# Connectors.net
KiCad netlist of a schematic drawn in Altium Designer
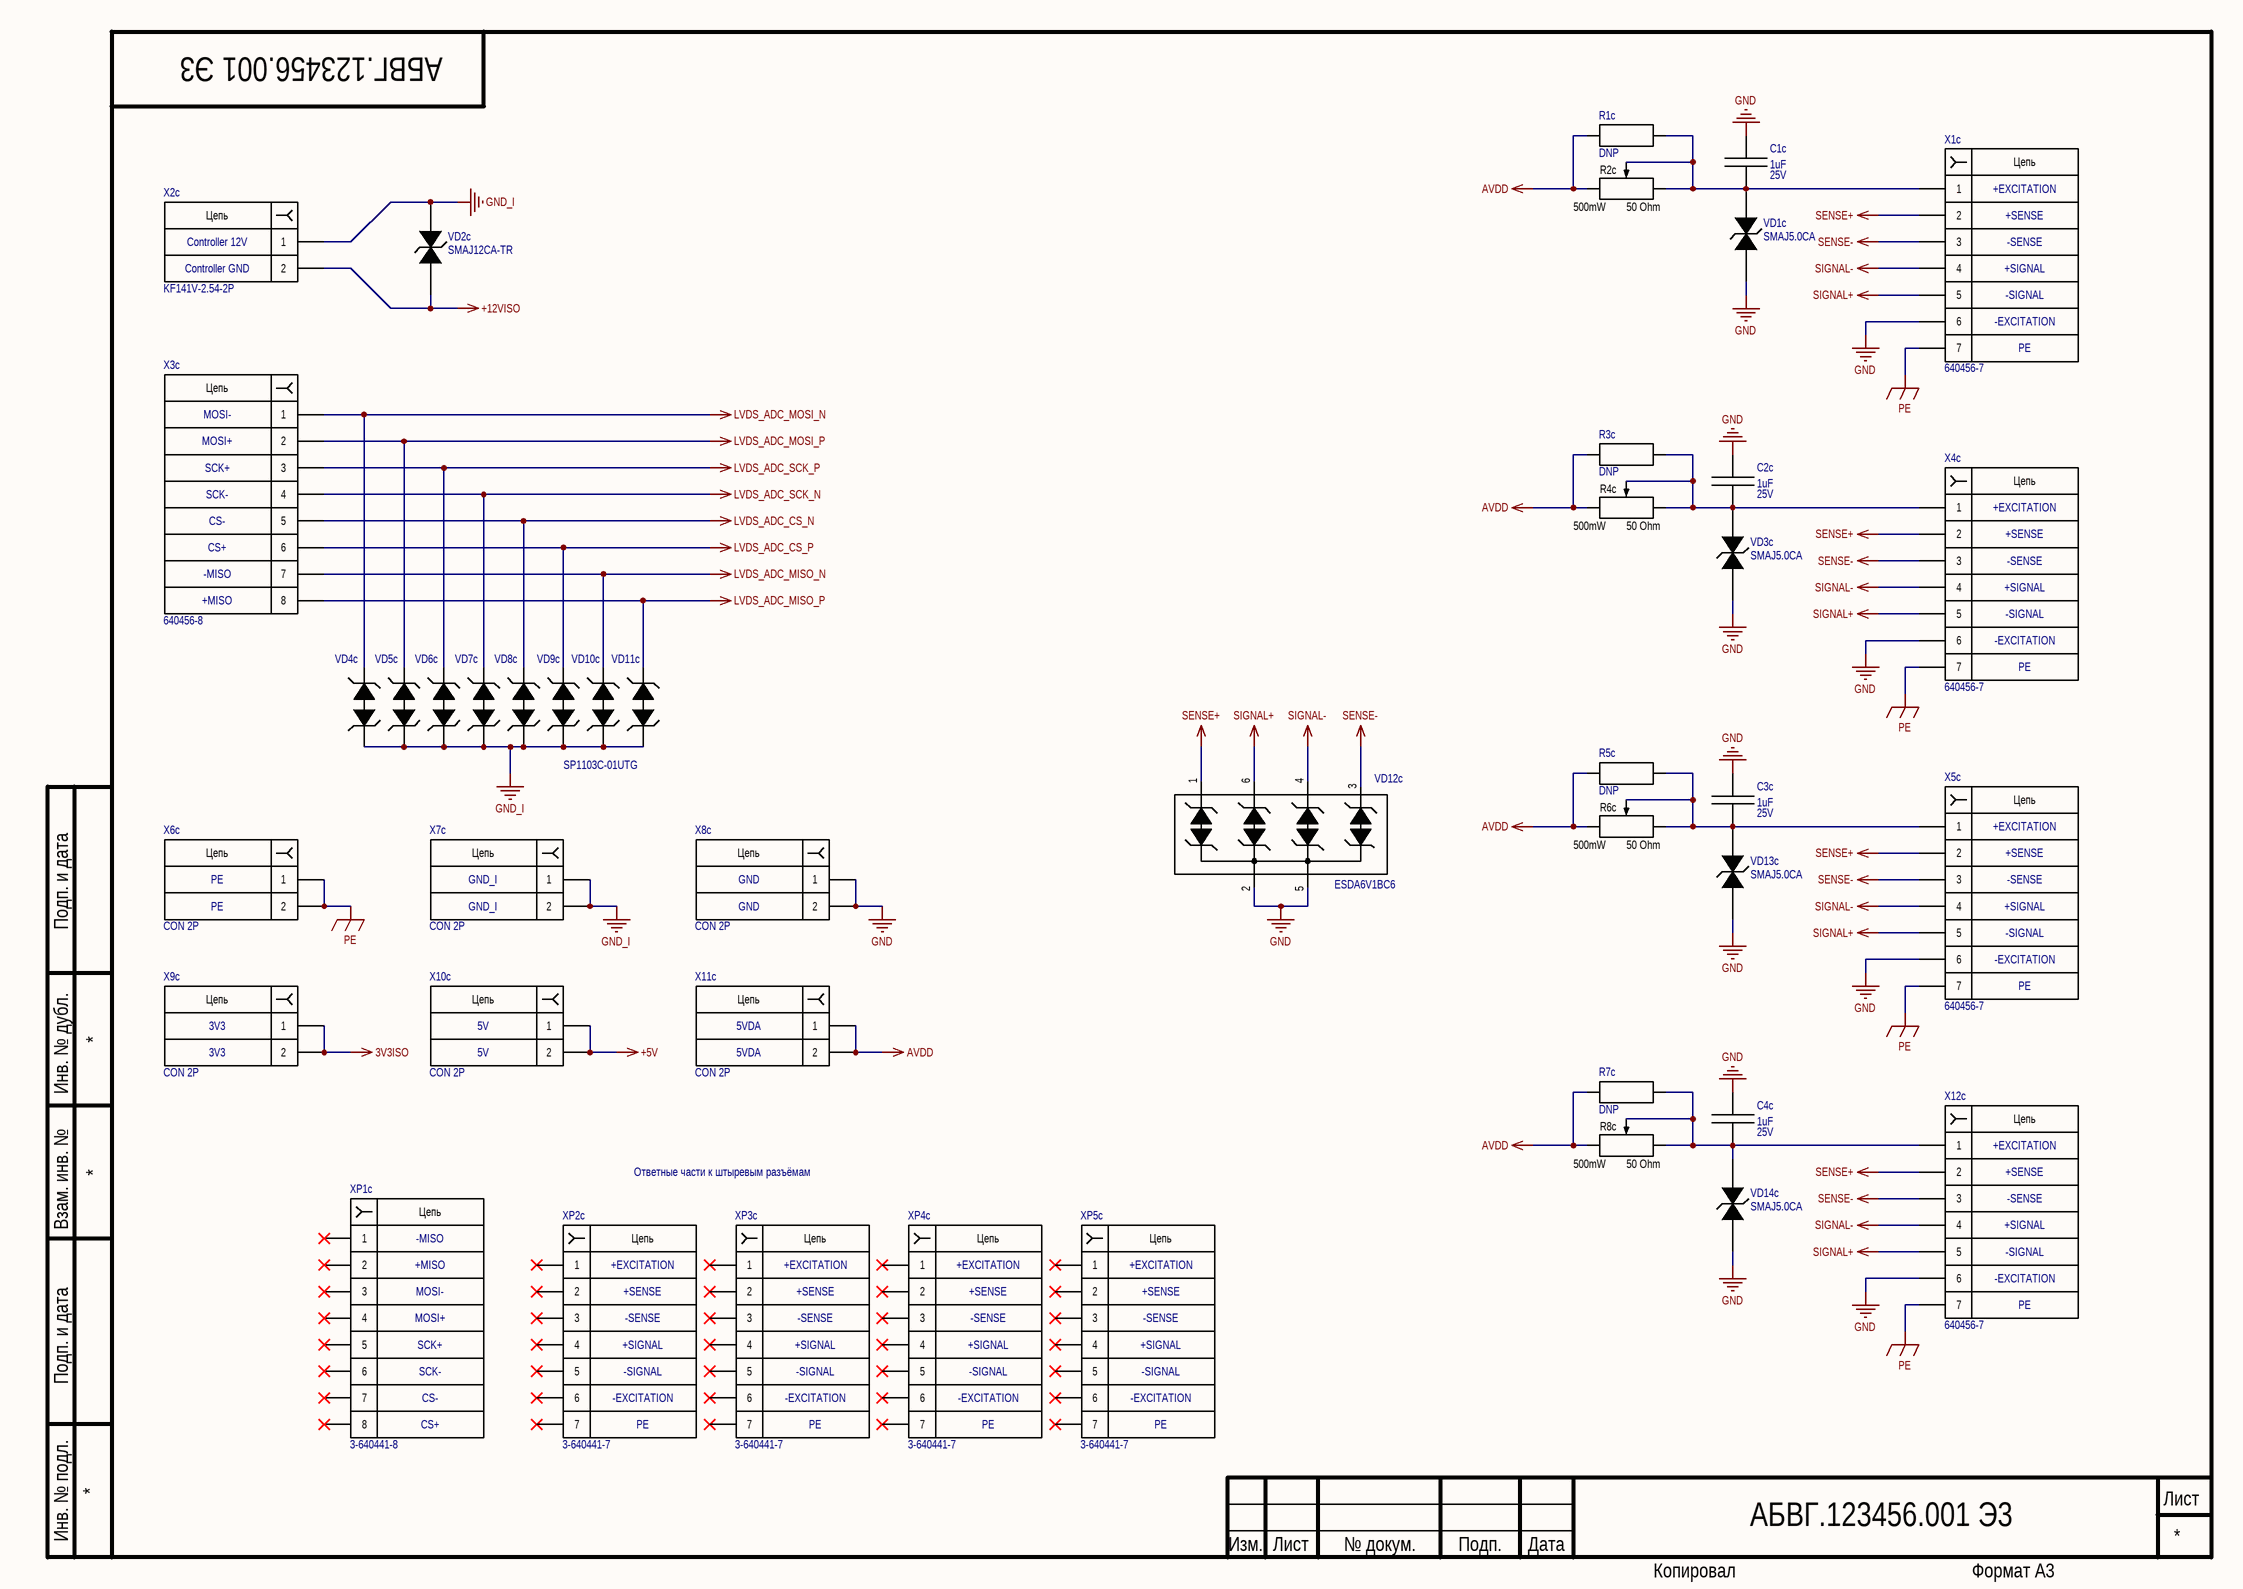
[diagram p0: Connectors.SchDoc]

(export (version "E")
  (design (tool "Eeschema 10.0.6"))
  (components
    (comp (ref "C1c")
      (value "TMK107BJ105KA-T")
      (footprint "CAP 0603 IPC MAX")
      (description "CAP SMD CER 1UF 25V X5R 0603")
      (fields
        (field (name "TOLERANCE") "10%")
        (field (name "CAPACITANCE") "1uF")
        (field (name "RATED VOLTAGE") "25V")
      )
      (libsource (lib "Passive components") (part "TMK107BJ105KA-T"))
    )
    (comp (ref "C2c")
      (value "TMK107BJ105KA-T")
      (footprint "CAP 0603 IPC MAX")
      (description "CAP SMD CER 1UF 25V X5R 0603")
      (fields
        (field (name "TOLERANCE") "10%")
        (field (name "CAPACITANCE") "1uF")
        (field (name "RATED VOLTAGE") "25V")
      )
      (libsource (lib "Passive components") (part "TMK107BJ105KA-T"))
    )
    (comp (ref "C3c")
      (value "TMK107BJ105KA-T")
      (footprint "CAP 0603 IPC MAX")
      (description "CAP SMD CER 1UF 25V X5R 0603")
      (fields
        (field (name "TOLERANCE") "10%")
        (field (name "CAPACITANCE") "1uF")
        (field (name "RATED VOLTAGE") "25V")
      )
      (libsource (lib "Passive components") (part "TMK107BJ105KA-T"))
    )
    (comp (ref "C4c")
      (value "TMK107BJ105KA-T")
      (footprint "CAP 0603 IPC MAX")
      (description "CAP SMD CER 1UF 25V X5R 0603")
      (fields
        (field (name "TOLERANCE") "10%")
        (field (name "CAPACITANCE") "1uF")
        (field (name "RATED VOLTAGE") "25V")
      )
      (libsource (lib "Passive components") (part "TMK107BJ105KA-T"))
    )
    (comp (ref "R1c")
      (value "DNP")
      (footprint "RES 0603 IPC MAX")
      (description "RES SMD/TH ?R (&K) OHM ?% ?W (PACKAGE)")
      (libsource (lib "Passive components") (part "RES GOST"))
    )
    (comp (ref "R2c")
      (value "PV36W500C01B00")
      (footprint "RES: 3296W")
      (description "TRIMMER 50 OHM 0.5W PC PIN TOP")
      (fields
        (field (name "TOLERANCE") "10%")
        (field (name "RATED POWER") "500mW")
        (field (name "RESISTANCE") "50 Ohm")
      )
      (libsource (lib "Passive components") (part "PV36W500C01B00"))
    )
    (comp (ref "R3c")
      (value "DNP")
      (footprint "RES 0603 IPC MAX")
      (description "RES SMD/TH ?R (&K) OHM ?% ?W (PACKAGE)")
      (libsource (lib "Passive components") (part "RES GOST"))
    )
    (comp (ref "R4c")
      (value "PV36W500C01B00")
      (footprint "RES: 3296W")
      (description "TRIMMER 50 OHM 0.5W PC PIN TOP")
      (fields
        (field (name "TOLERANCE") "10%")
        (field (name "RATED POWER") "500mW")
        (field (name "RESISTANCE") "50 Ohm")
      )
      (libsource (lib "Passive components") (part "PV36W500C01B00"))
    )
    (comp (ref "R5c")
      (value "DNP")
      (footprint "RES 0603 IPC MAX")
      (description "RES SMD/TH ?R (&K) OHM ?% ?W (PACKAGE)")
      (libsource (lib "Passive components") (part "RES GOST"))
    )
    (comp (ref "R6c")
      (value "PV36W500C01B00")
      (footprint "RES: 3296W")
      (description "TRIMMER 50 OHM 0.5W PC PIN TOP")
      (fields
        (field (name "TOLERANCE") "10%")
        (field (name "RATED POWER") "500mW")
        (field (name "RESISTANCE") "50 Ohm")
      )
      (libsource (lib "Passive components") (part "PV36W500C01B00"))
    )
    (comp (ref "R7c")
      (value "DNP")
      (footprint "RES 0603 IPC MAX")
      (description "RES SMD/TH ?R (&K) OHM ?% ?W (PACKAGE)")
      (libsource (lib "Passive components") (part "RES GOST"))
    )
    (comp (ref "R8c")
      (value "PV36W500C01B00")
      (footprint "RES: 3296W")
      (description "TRIMMER 50 OHM 0.5W PC PIN TOP")
      (fields
        (field (name "TOLERANCE") "10%")
        (field (name "RATED POWER") "500mW")
        (field (name "RESISTANCE") "50 Ohm")
      )
      (libsource (lib "Passive components") (part "PV36W500C01B00"))
    )
    (comp (ref "VD1c")
      (value "SMAJ5.0CA")
      (footprint "DO-214AC Bidirectional")
      (description "TVS DIODE 5VWM 9.2VC DO214AC")
      (libsource (lib "Diodes") (part "SMAJ5.0CA"))
    )
    (comp (ref "VD2c")
      (value "SMAJ12CA-TR")
      (footprint "DO-214AC Bidirectional")
      (description "TVS DIODE 12VWM 25.3VC SMA")
      (libsource (lib "Diodes") (part "SMAJ12CA-TR"))
    )
    (comp (ref "VD3c")
      (value "SMAJ5.0CA")
      (footprint "DO-214AC Bidirectional")
      (description "TVS DIODE 5VWM 9.2VC DO214AC")
      (libsource (lib "Diodes") (part "SMAJ5.0CA"))
    )
    (comp (ref "VD4c")
      (value "SP1103C-01UTG")
      (footprint "2-DFN 1.6x1.0")
      (description "TVS DIODE 3.3VWM 9VC 2DFN")
      (libsource (lib "Diodes") (part "SP1103C-01UTG"))
    )
    (comp (ref "VD5c")
      (value "SP1103C-01UTG")
      (footprint "2-DFN 1.6x1.0")
      (description "TVS DIODE 3.3VWM 9VC 2DFN")
      (libsource (lib "Diodes") (part "SP1103C-01UTG"))
    )
    (comp (ref "VD6c")
      (value "SP1103C-01UTG")
      (footprint "2-DFN 1.6x1.0")
      (description "TVS DIODE 3.3VWM 9VC 2DFN")
      (libsource (lib "Diodes") (part "SP1103C-01UTG"))
    )
    (comp (ref "VD7c")
      (value "SP1103C-01UTG")
      (footprint "2-DFN 1.6x1.0")
      (description "TVS DIODE 3.3VWM 9VC 2DFN")
      (libsource (lib "Diodes") (part "SP1103C-01UTG"))
    )
    (comp (ref "VD8c")
      (value "SP1103C-01UTG")
      (footprint "2-DFN 1.6x1.0")
      (description "TVS DIODE 3.3VWM 9VC 2DFN")
      (libsource (lib "Diodes") (part "SP1103C-01UTG"))
    )
    (comp (ref "VD9c")
      (value "SP1103C-01UTG")
      (footprint "2-DFN 1.6x1.0")
      (description "TVS DIODE 3.3VWM 9VC 2DFN")
      (libsource (lib "Diodes") (part "SP1103C-01UTG"))
    )
    (comp (ref "VD10c")
      (value "SP1103C-01UTG")
      (footprint "2-DFN 1.6x1.0")
      (description "TVS DIODE 3.3VWM 9VC 2DFN")
      (libsource (lib "Diodes") (part "SP1103C-01UTG"))
    )
    (comp (ref "VD11c")
      (value "SP1103C-01UTG")
      (footprint "2-DFN 1.6x1.0")
      (description "TVS DIODE 3.3VWM 9VC 2DFN")
      (libsource (lib "Diodes") (part "SP1103C-01UTG"))
    )
    (comp (ref "VD12c")
      (value "ESDA6V1BC6")
      (footprint "SOT-23-6")
      (description "TVS DIODE 5VWM SOT23-6")
      (libsource (lib "Diodes") (part "ESDA6V1BC6"))
    )
    (comp (ref "VD13c")
      (value "SMAJ5.0CA")
      (footprint "DO-214AC Bidirectional")
      (description "TVS DIODE 5VWM 9.2VC DO214AC")
      (libsource (lib "Diodes") (part "SMAJ5.0CA"))
    )
    (comp (ref "VD14c")
      (value "SMAJ5.0CA")
      (footprint "DO-214AC Bidirectional")
      (description "TVS DIODE 5VWM 9.2VC DO214AC")
      (libsource (lib "Diodes") (part "SMAJ5.0CA"))
    )
    (comp (ref "X1c")
      (value "640456-7")
      (footprint "640456-7")
      (description "CONN HEADER VERT 7POS 2.54MM")
      (libsource (lib "Connectors") (part "640456-7"))
    )
    (comp (ref "X2c")
      (value "KF141V-2.54-2P")
      (footprint "KF141V-2.54-2P")
      (description "TERMINAL BLOCK 2 PIN 2.54mm 2A 150V T/H")
      (libsource (lib "Connectors") (part "KF141V-2.54-2P"))
    )
    (comp (ref "X3c")
      (value "640456-8")
      (footprint "640456-8")
      (description "CONN HEADER VERT 8POS 2.54MM")
      (libsource (lib "Connectors") (part "640456-8"))
    )
    (comp (ref "X4c")
      (value "640456-7")
      (footprint "640456-7")
      (description "CONN HEADER VERT 7POS 2.54MM")
      (libsource (lib "Connectors") (part "640456-7"))
    )
    (comp (ref "X5c")
      (value "640456-7")
      (footprint "640456-7")
      (description "CONN HEADER VERT 7POS 2.54MM")
      (libsource (lib "Connectors") (part "640456-7"))
    )
    (comp (ref "X6c")
      (value "CON 2P")
      (footprint "2P TH 2.54mm")
      (libsource (lib "Connectors") (part "2P CONNECTOR"))
    )
    (comp (ref "X7c")
      (value "CON 2P")
      (footprint "2P TH 2.54mm")
      (libsource (lib "Connectors") (part "2P CONNECTOR"))
    )
    (comp (ref "X8c")
      (value "CON 2P")
      (footprint "2P TH 2.54mm")
      (libsource (lib "Connectors") (part "2P CONNECTOR"))
    )
    (comp (ref "X9c")
      (value "CON 2P")
      (footprint "2P TH 2.54mm")
      (libsource (lib "Connectors") (part "2P CONNECTOR"))
    )
    (comp (ref "X10c")
      (value "CON 2P")
      (footprint "2P TH 2.54mm")
      (libsource (lib "Connectors") (part "2P CONNECTOR"))
    )
    (comp (ref "X11c")
      (value "CON 2P")
      (footprint "2P TH 2.54mm")
      (libsource (lib "Connectors") (part "2P CONNECTOR"))
    )
    (comp (ref "X12c")
      (value "640456-7")
      (footprint "640456-7")
      (description "CONN HEADER VERT 7POS 2.54MM")
      (libsource (lib "Connectors") (part "640456-7"))
    )
    (comp (ref "XP1c")
      (value "3-640441-8")
      (description "CONN RCPT 8POS IDC 24AWG TIN")
      (libsource (lib "Connectors") (part "3-640441-8"))
    )
    (comp (ref "XP2c")
      (value "3-640441-7")
      (description "CONN RCPT 7POS IDC 24AWG TIN")
      (libsource (lib "Connectors") (part "3-640441-7"))
    )
    (comp (ref "XP3c")
      (value "3-640441-7")
      (description "CONN RCPT 7POS IDC 24AWG TIN")
      (libsource (lib "Connectors") (part "3-640441-7"))
    )
    (comp (ref "XP4c")
      (value "3-640441-7")
      (description "CONN RCPT 7POS IDC 24AWG TIN")
      (libsource (lib "Connectors") (part "3-640441-7"))
    )
    (comp (ref "XP5c")
      (value "3-640441-7")
      (description "CONN RCPT 7POS IDC 24AWG TIN")
      (libsource (lib "Connectors") (part "3-640441-7"))
    )
  )
  (nets
    (net (code "1") (name "+5V") (class "Default")
      (node (ref "X10c") (pin "1") (pinfunction "1_1") (pintype "passive"))
      (node (ref "X10c") (pin "2") (pinfunction "2_2") (pintype "passive"))
    )
    (net (code "2") (name "+12VISO") (class "Default")
      (node (ref "VD2c") (pin "1") (pinfunction "1_1") (pintype "passive"))
      (node (ref "X2c") (pin "2") (pinfunction "2_2") (pintype "passive"))
    )
    (net (code "3") (name "3V3ISO") (class "Default")
      (node (ref "X9c") (pin "1") (pinfunction "1_1") (pintype "passive"))
      (node (ref "X9c") (pin "2") (pinfunction "2_2") (pintype "passive"))
    )
    (net (code "4") (name "AVDD") (class "Default")
      (node (ref "R1c") (pin "1") (pinfunction "1_1") (pintype "passive"))
      (node (ref "R2c") (pin "1") (pinfunction "1_1") (pintype "passive"))
      (node (ref "R3c") (pin "1") (pinfunction "1_1") (pintype "passive"))
      (node (ref "R4c") (pin "1") (pinfunction "1_1") (pintype "passive"))
      (node (ref "R5c") (pin "1") (pinfunction "1_1") (pintype "passive"))
      (node (ref "R6c") (pin "1") (pinfunction "1_1") (pintype "passive"))
      (node (ref "R7c") (pin "1") (pinfunction "1_1") (pintype "passive"))
      (node (ref "R8c") (pin "1") (pinfunction "1_1") (pintype "passive"))
      (node (ref "X11c") (pin "1") (pinfunction "1_1") (pintype "passive"))
      (node (ref "X11c") (pin "2") (pinfunction "2_2") (pintype "passive"))
    )
    (net (code "5") (name "GND") (class "Default")
      (node (ref "C1c") (pin "1") (pinfunction "1_1") (pintype "passive"))
      (node (ref "C2c") (pin "1") (pinfunction "1_1") (pintype "passive"))
      (node (ref "C3c") (pin "1") (pinfunction "1_1") (pintype "passive"))
      (node (ref "C4c") (pin "1") (pinfunction "1_1") (pintype "passive"))
      (node (ref "VD12c") (pin "2") (pinfunction "2_2") (pintype "passive"))
      (node (ref "VD12c") (pin "5") (pinfunction "5_5") (pintype "passive"))
      (node (ref "VD13c") (pin "1") (pinfunction "1_1") (pintype "passive"))
      (node (ref "VD14c") (pin "1") (pinfunction "1_1") (pintype "passive"))
      (node (ref "VD1c") (pin "1") (pinfunction "1_1") (pintype "passive"))
      (node (ref "VD3c") (pin "1") (pinfunction "1_1") (pintype "passive"))
      (node (ref "X12c") (pin "6") (pinfunction "6_6") (pintype "passive"))
      (node (ref "X1c") (pin "6") (pinfunction "6_6") (pintype "passive"))
      (node (ref "X4c") (pin "6") (pinfunction "6_6") (pintype "passive"))
      (node (ref "X5c") (pin "6") (pinfunction "6_6") (pintype "passive"))
      (node (ref "X8c") (pin "1") (pinfunction "1_1") (pintype "passive"))
      (node (ref "X8c") (pin "2") (pinfunction "2_2") (pintype "passive"))
    )
    (net (code "6") (name "GND_I") (class "Default")
      (node (ref "VD10c") (pin "1") (pinfunction "1_1") (pintype "passive"))
      (node (ref "VD11c") (pin "1") (pinfunction "1_1") (pintype "passive"))
      (node (ref "VD2c") (pin "2") (pinfunction "2_2") (pintype "passive"))
      (node (ref "VD4c") (pin "1") (pinfunction "1_1") (pintype "passive"))
      (node (ref "VD5c") (pin "1") (pinfunction "1_1") (pintype "passive"))
      (node (ref "VD6c") (pin "1") (pinfunction "1_1") (pintype "passive"))
      (node (ref "VD7c") (pin "1") (pinfunction "1_1") (pintype "passive"))
      (node (ref "VD8c") (pin "1") (pinfunction "1_1") (pintype "passive"))
      (node (ref "VD9c") (pin "1") (pinfunction "1_1") (pintype "passive"))
      (node (ref "X2c") (pin "1") (pinfunction "1_1") (pintype "passive"))
      (node (ref "X7c") (pin "1") (pinfunction "1_1") (pintype "passive"))
      (node (ref "X7c") (pin "2") (pinfunction "2_2") (pintype "passive"))
    )
    (net (code "7") (name "LVDS_ADC_CS_N") (class "Default")
      (node (ref "VD8c") (pin "2") (pinfunction "2_2") (pintype "passive"))
      (node (ref "X3c") (pin "5") (pinfunction "5_5") (pintype "passive"))
    )
    (net (code "8") (name "LVDS_ADC_CS_P") (class "Default")
      (node (ref "VD9c") (pin "2") (pinfunction "2_2") (pintype "passive"))
      (node (ref "X3c") (pin "6") (pinfunction "6_6") (pintype "passive"))
    )
    (net (code "9") (name "LVDS_ADC_MISO_N") (class "Default")
      (node (ref "VD10c") (pin "2") (pinfunction "2_2") (pintype "passive"))
      (node (ref "X3c") (pin "7") (pinfunction "7_7") (pintype "passive"))
    )
    (net (code "10") (name "LVDS_ADC_MISO_P") (class "Default")
      (node (ref "VD11c") (pin "2") (pinfunction "2_2") (pintype "passive"))
      (node (ref "X3c") (pin "8") (pinfunction "8_8") (pintype "passive"))
    )
    (net (code "11") (name "LVDS_ADC_MOSI_N") (class "Default")
      (node (ref "VD4c") (pin "2") (pinfunction "2_2") (pintype "passive"))
      (node (ref "X3c") (pin "1") (pinfunction "1_1") (pintype "passive"))
    )
    (net (code "12") (name "LVDS_ADC_MOSI_P") (class "Default")
      (node (ref "VD5c") (pin "2") (pinfunction "2_2") (pintype "passive"))
      (node (ref "X3c") (pin "2") (pinfunction "2_2") (pintype "passive"))
    )
    (net (code "13") (name "LVDS_ADC_SCK_N") (class "Default")
      (node (ref "VD7c") (pin "2") (pinfunction "2_2") (pintype "passive"))
      (node (ref "X3c") (pin "4") (pinfunction "4_4") (pintype "passive"))
    )
    (net (code "14") (name "LVDS_ADC_SCK_P") (class "Default")
      (node (ref "VD6c") (pin "2") (pinfunction "2_2") (pintype "passive"))
      (node (ref "X3c") (pin "3") (pinfunction "3_3") (pintype "passive"))
    )
    (net (code "15") (name "Net-(C1c-Pad2)") (class "Default")
      (node (ref "C1c") (pin "2") (pinfunction "2_2") (pintype "passive"))
      (node (ref "R1c") (pin "2") (pinfunction "2_2") (pintype "passive"))
      (node (ref "R2c") (pin "2") (pinfunction "2_2") (pintype "passive"))
      (node (ref "R2c") (pin "3") (pinfunction "3_3") (pintype "passive"))
      (node (ref "VD1c") (pin "2") (pinfunction "2_2") (pintype "passive"))
      (node (ref "X1c") (pin "1") (pinfunction "1_1") (pintype "passive"))
    )
    (net (code "16") (name "Net-(C2c-Pad2)") (class "Default")
      (node (ref "C2c") (pin "2") (pinfunction "2_2") (pintype "passive"))
      (node (ref "R3c") (pin "2") (pinfunction "2_2") (pintype "passive"))
      (node (ref "R4c") (pin "2") (pinfunction "2_2") (pintype "passive"))
      (node (ref "R4c") (pin "3") (pinfunction "3_3") (pintype "passive"))
      (node (ref "VD3c") (pin "2") (pinfunction "2_2") (pintype "passive"))
      (node (ref "X4c") (pin "1") (pinfunction "1_1") (pintype "passive"))
    )
    (net (code "17") (name "Net-(C3c-Pad2)") (class "Default")
      (node (ref "C3c") (pin "2") (pinfunction "2_2") (pintype "passive"))
      (node (ref "R5c") (pin "2") (pinfunction "2_2") (pintype "passive"))
      (node (ref "R6c") (pin "2") (pinfunction "2_2") (pintype "passive"))
      (node (ref "R6c") (pin "3") (pinfunction "3_3") (pintype "passive"))
      (node (ref "VD13c") (pin "2") (pinfunction "2_2") (pintype "passive"))
      (node (ref "X5c") (pin "1") (pinfunction "1_1") (pintype "passive"))
    )
    (net (code "18") (name "Net-(C4c-Pad2)") (class "Default")
      (node (ref "C4c") (pin "2") (pinfunction "2_2") (pintype "passive"))
      (node (ref "R7c") (pin "2") (pinfunction "2_2") (pintype "passive"))
      (node (ref "R8c") (pin "2") (pinfunction "2_2") (pintype "passive"))
      (node (ref "R8c") (pin "3") (pinfunction "3_3") (pintype "passive"))
      (node (ref "VD14c") (pin "2") (pinfunction "2_2") (pintype "passive"))
      (node (ref "X12c") (pin "1") (pinfunction "1_1") (pintype "passive"))
    )
    (net (code "19") (name "PE") (class "Default")
      (node (ref "X12c") (pin "7") (pinfunction "7_7") (pintype "passive"))
      (node (ref "X1c") (pin "7") (pinfunction "7_7") (pintype "passive"))
      (node (ref "X4c") (pin "7") (pinfunction "7_7") (pintype "passive"))
      (node (ref "X5c") (pin "7") (pinfunction "7_7") (pintype "passive"))
      (node (ref "X6c") (pin "1") (pinfunction "1_1") (pintype "passive"))
      (node (ref "X6c") (pin "2") (pinfunction "2_2") (pintype "passive"))
    )
    (net (code "20") (name "SENSE+") (class "Default")
      (node (ref "VD12c") (pin "1") (pinfunction "1_1") (pintype "passive"))
      (node (ref "X12c") (pin "2") (pinfunction "2_2") (pintype "passive"))
      (node (ref "X1c") (pin "2") (pinfunction "2_2") (pintype "passive"))
      (node (ref "X4c") (pin "2") (pinfunction "2_2") (pintype "passive"))
      (node (ref "X5c") (pin "2") (pinfunction "2_2") (pintype "passive"))
    )
    (net (code "21") (name "SENSE-") (class "Default")
      (node (ref "VD12c") (pin "3") (pinfunction "3_3") (pintype "passive"))
      (node (ref "X12c") (pin "3") (pinfunction "3_3") (pintype "passive"))
      (node (ref "X1c") (pin "3") (pinfunction "3_3") (pintype "passive"))
      (node (ref "X4c") (pin "3") (pinfunction "3_3") (pintype "passive"))
      (node (ref "X5c") (pin "3") (pinfunction "3_3") (pintype "passive"))
    )
    (net (code "22") (name "SIGNAL+") (class "Default")
      (node (ref "VD12c") (pin "6") (pinfunction "6_6") (pintype "passive"))
      (node (ref "X12c") (pin "5") (pinfunction "5_5") (pintype "passive"))
      (node (ref "X1c") (pin "5") (pinfunction "5_5") (pintype "passive"))
      (node (ref "X4c") (pin "5") (pinfunction "5_5") (pintype "passive"))
      (node (ref "X5c") (pin "5") (pinfunction "5_5") (pintype "passive"))
    )
    (net (code "23") (name "SIGNAL-") (class "Default")
      (node (ref "VD12c") (pin "4") (pinfunction "4_4") (pintype "passive"))
      (node (ref "X12c") (pin "4") (pinfunction "4_4") (pintype "passive"))
      (node (ref "X1c") (pin "4") (pinfunction "4_4") (pintype "passive"))
      (node (ref "X4c") (pin "4") (pinfunction "4_4") (pintype "passive"))
      (node (ref "X5c") (pin "4") (pinfunction "4_4") (pintype "passive"))
    )
    (net (code "24") (name "unconnected-(XP1c-Pad1)") (class "Default")
      (node (ref "XP1c") (pin "1") (pinfunction "1_1") (pintype "passive+no_connect"))
    )
    (net (code "25") (name "unconnected-(XP1c-Pad2)") (class "Default")
      (node (ref "XP1c") (pin "2") (pinfunction "2_2") (pintype "passive+no_connect"))
    )
    (net (code "26") (name "unconnected-(XP1c-Pad3)") (class "Default")
      (node (ref "XP1c") (pin "3") (pinfunction "3_3") (pintype "passive+no_connect"))
    )
    (net (code "27") (name "unconnected-(XP1c-Pad4)") (class "Default")
      (node (ref "XP1c") (pin "4") (pinfunction "4_4") (pintype "passive+no_connect"))
    )
    (net (code "28") (name "unconnected-(XP1c-Pad5)") (class "Default")
      (node (ref "XP1c") (pin "5") (pinfunction "5_5") (pintype "passive+no_connect"))
    )
    (net (code "29") (name "unconnected-(XP1c-Pad6)") (class "Default")
      (node (ref "XP1c") (pin "6") (pinfunction "6_6") (pintype "passive+no_connect"))
    )
    (net (code "30") (name "unconnected-(XP1c-Pad7)") (class "Default")
      (node (ref "XP1c") (pin "7") (pinfunction "7_7") (pintype "passive+no_connect"))
    )
    (net (code "31") (name "unconnected-(XP1c-Pad8)") (class "Default")
      (node (ref "XP1c") (pin "8") (pinfunction "8_8") (pintype "passive+no_connect"))
    )
    (net (code "32") (name "unconnected-(XP2c-Pad1)") (class "Default")
      (node (ref "XP2c") (pin "1") (pinfunction "1_1") (pintype "passive+no_connect"))
    )
    (net (code "33") (name "unconnected-(XP2c-Pad2)") (class "Default")
      (node (ref "XP2c") (pin "2") (pinfunction "2_2") (pintype "passive+no_connect"))
    )
    (net (code "34") (name "unconnected-(XP2c-Pad3)") (class "Default")
      (node (ref "XP2c") (pin "3") (pinfunction "3_3") (pintype "passive+no_connect"))
    )
    (net (code "35") (name "unconnected-(XP2c-Pad4)") (class "Default")
      (node (ref "XP2c") (pin "4") (pinfunction "4_4") (pintype "passive+no_connect"))
    )
    (net (code "36") (name "unconnected-(XP2c-Pad5)") (class "Default")
      (node (ref "XP2c") (pin "5") (pinfunction "5_5") (pintype "passive+no_connect"))
    )
    (net (code "37") (name "unconnected-(XP2c-Pad6)") (class "Default")
      (node (ref "XP2c") (pin "6") (pinfunction "6_6") (pintype "passive+no_connect"))
    )
    (net (code "38") (name "unconnected-(XP2c-Pad7)") (class "Default")
      (node (ref "XP2c") (pin "7") (pinfunction "7_7") (pintype "passive+no_connect"))
    )
    (net (code "39") (name "unconnected-(XP3c-Pad1)") (class "Default")
      (node (ref "XP3c") (pin "1") (pinfunction "1_1") (pintype "passive+no_connect"))
    )
    (net (code "40") (name "unconnected-(XP3c-Pad2)") (class "Default")
      (node (ref "XP3c") (pin "2") (pinfunction "2_2") (pintype "passive+no_connect"))
    )
    (net (code "41") (name "unconnected-(XP3c-Pad3)") (class "Default")
      (node (ref "XP3c") (pin "3") (pinfunction "3_3") (pintype "passive+no_connect"))
    )
    (net (code "42") (name "unconnected-(XP3c-Pad4)") (class "Default")
      (node (ref "XP3c") (pin "4") (pinfunction "4_4") (pintype "passive+no_connect"))
    )
    (net (code "43") (name "unconnected-(XP3c-Pad5)") (class "Default")
      (node (ref "XP3c") (pin "5") (pinfunction "5_5") (pintype "passive+no_connect"))
    )
    (net (code "44") (name "unconnected-(XP3c-Pad6)") (class "Default")
      (node (ref "XP3c") (pin "6") (pinfunction "6_6") (pintype "passive+no_connect"))
    )
    (net (code "45") (name "unconnected-(XP3c-Pad7)") (class "Default")
      (node (ref "XP3c") (pin "7") (pinfunction "7_7") (pintype "passive+no_connect"))
    )
    (net (code "46") (name "unconnected-(XP4c-Pad1)") (class "Default")
      (node (ref "XP4c") (pin "1") (pinfunction "1_1") (pintype "passive+no_connect"))
    )
    (net (code "47") (name "unconnected-(XP4c-Pad2)") (class "Default")
      (node (ref "XP4c") (pin "2") (pinfunction "2_2") (pintype "passive+no_connect"))
    )
    (net (code "48") (name "unconnected-(XP4c-Pad3)") (class "Default")
      (node (ref "XP4c") (pin "3") (pinfunction "3_3") (pintype "passive+no_connect"))
    )
    (net (code "49") (name "unconnected-(XP4c-Pad4)") (class "Default")
      (node (ref "XP4c") (pin "4") (pinfunction "4_4") (pintype "passive+no_connect"))
    )
    (net (code "50") (name "unconnected-(XP4c-Pad5)") (class "Default")
      (node (ref "XP4c") (pin "5") (pinfunction "5_5") (pintype "passive+no_connect"))
    )
    (net (code "51") (name "unconnected-(XP4c-Pad6)") (class "Default")
      (node (ref "XP4c") (pin "6") (pinfunction "6_6") (pintype "passive+no_connect"))
    )
    (net (code "52") (name "unconnected-(XP4c-Pad7)") (class "Default")
      (node (ref "XP4c") (pin "7") (pinfunction "7_7") (pintype "passive+no_connect"))
    )
    (net (code "53") (name "unconnected-(XP5c-Pad1)") (class "Default")
      (node (ref "XP5c") (pin "1") (pinfunction "1_1") (pintype "passive+no_connect"))
    )
    (net (code "54") (name "unconnected-(XP5c-Pad2)") (class "Default")
      (node (ref "XP5c") (pin "2") (pinfunction "2_2") (pintype "passive+no_connect"))
    )
    (net (code "55") (name "unconnected-(XP5c-Pad3)") (class "Default")
      (node (ref "XP5c") (pin "3") (pinfunction "3_3") (pintype "passive+no_connect"))
    )
    (net (code "56") (name "unconnected-(XP5c-Pad4)") (class "Default")
      (node (ref "XP5c") (pin "4") (pinfunction "4_4") (pintype "passive+no_connect"))
    )
    (net (code "57") (name "unconnected-(XP5c-Pad5)") (class "Default")
      (node (ref "XP5c") (pin "5") (pinfunction "5_5") (pintype "passive+no_connect"))
    )
    (net (code "58") (name "unconnected-(XP5c-Pad6)") (class "Default")
      (node (ref "XP5c") (pin "6") (pinfunction "6_6") (pintype "passive+no_connect"))
    )
    (net (code "59") (name "unconnected-(XP5c-Pad7)") (class "Default")
      (node (ref "XP5c") (pin "7") (pinfunction "7_7") (pintype "passive+no_connect"))
    )
  )
)
